# MAX232_0-99_Counter.net
KiCad netlist of a schematic drawn in Altium Designer
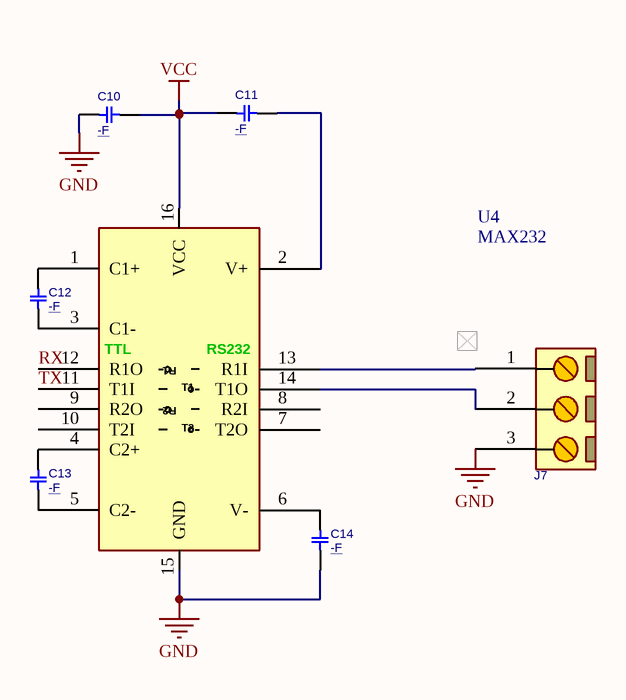
[diagram p0: MAX232_0-99_Counter.SchDoc]

(export (version "E")
  (design (tool "Eeschema 10.0.6"))
  (components
    (comp (ref "C10")
      (value "-F")
      (footprint "C0805")
      (description "CAP, MLCC, -F, -V, MATERIAL, -%, 0201")
      (fields (field (name "MANF_P#") "MANF_PART#"))
      (libsource (lib "all_lib") (part "CAP_SMD_MLCC_0805"))
    )
    (comp (ref "C11")
      (value "-F")
      (footprint "C0805")
      (description "CAP, MLCC, -F, -V, MATERIAL, -%, 0201")
      (fields (field (name "MANF_P#") "MANF_PART#"))
      (libsource (lib "all_lib") (part "CAP_SMD_MLCC_0805"))
    )
    (comp (ref "C12")
      (value "-F")
      (footprint "C0805")
      (description "CAP, MLCC, -F, -V, MATERIAL, -%, 0201")
      (fields (field (name "MANF_P#") "MANF_PART#"))
      (libsource (lib "all_lib") (part "CAP_SMD_MLCC_0805"))
    )
    (comp (ref "C13")
      (value "-F")
      (footprint "C0805")
      (description "CAP, MLCC, -F, -V, MATERIAL, -%, 0201")
      (fields (field (name "MANF_P#") "MANF_PART#"))
      (libsource (lib "all_lib") (part "CAP_SMD_MLCC_0805"))
    )
    (comp (ref "C14")
      (value "-F")
      (footprint "C0805")
      (description "CAP, MLCC, -F, -V, MATERIAL, -%, 0201")
      (fields (field (name "MANF_P#") "MANF_PART#"))
      (libsource (lib "all_lib") (part "CAP_SMD_MLCC_0805"))
    )
    (comp (ref "J7")
      (value "CONN_TB3")
      (footprint "MSTB_3")
      (description "CONN, PHOENIX MSTB, 5-G, 5.08mm pitch")
      (libsource (lib "all_lib") (part "CONN_MSTB_3"))
    )
    (comp (ref "U4")
      (value "MAX232")
      (footprint "SO_16")
      (description "RS-232, DUAL, +5V, Driver/Receiver")
      (fields (field (name "MANF") "Maxim Integrated") (field (name "MANF_PART#") "MAX232ACSE"))
      (libsource (lib "all_lib") (part "MAX232_SOP16"))
    )
  )
  (nets
    (net (code "1") (name "/RX") (class "Default")
      (node (ref "U4") (pin "12") (pinfunction "R1O_12") (pintype "passive"))
    )
    (net (code "2") (name "/TX") (class "Default")
      (node (ref "U4") (pin "11") (pinfunction "T1I_11") (pintype "passive"))
    )
    (net (code "3") (name "GND") (class "Default")
      (node (ref "C10") (pin "1") (pinfunction "1_1") (pintype "passive"))
      (node (ref "C14") (pin "1") (pinfunction "1_1") (pintype "passive"))
      (node (ref "J7") (pin "3") (pinfunction "3_3") (pintype "passive"))
      (node (ref "U4") (pin "15") (pinfunction "GND_15") (pintype "power_in"))
    )
    (net (code "4") (name "Net-(U4-C1+)") (class "Default")
      (node (ref "C12") (pin "2") (pinfunction "2_2") (pintype "passive"))
      (node (ref "U4") (pin "1") (pinfunction "C1+_1") (pintype "passive"))
    )
    (net (code "5") (name "Net-(U4-C1-)") (class "Default")
      (node (ref "C12") (pin "1") (pinfunction "1_1") (pintype "passive"))
      (node (ref "U4") (pin "3") (pinfunction "C1-_3") (pintype "passive"))
    )
    (net (code "6") (name "Net-(U4-C2+)") (class "Default")
      (node (ref "C13") (pin "2") (pinfunction "2_2") (pintype "passive"))
      (node (ref "U4") (pin "4") (pinfunction "C2+_4") (pintype "passive"))
    )
    (net (code "7") (name "Net-(U4-C2-)") (class "Default")
      (node (ref "C13") (pin "1") (pinfunction "1_1") (pintype "passive"))
      (node (ref "U4") (pin "5") (pinfunction "C2-_5") (pintype "passive"))
    )
    (net (code "8") (name "Net-(U4-R1I)") (class "Default")
      (node (ref "J7") (pin "1") (pinfunction "1_1") (pintype "passive"))
      (node (ref "U4") (pin "13") (pinfunction "R1I_13") (pintype "passive"))
    )
    (net (code "9") (name "Net-(U4-T1O)") (class "Default")
      (node (ref "J7") (pin "2") (pinfunction "2_2") (pintype "passive"))
      (node (ref "U4") (pin "14") (pinfunction "T1O_14") (pintype "passive"))
    )
    (net (code "10") (name "Net-(U4-V+)") (class "Default")
      (node (ref "C11") (pin "2") (pinfunction "2_2") (pintype "passive"))
      (node (ref "U4") (pin "2") (pinfunction "V+_2") (pintype "passive"))
    )
    (net (code "11") (name "Net-(U4-V-)") (class "Default")
      (node (ref "C14") (pin "2") (pinfunction "2_2") (pintype "passive"))
      (node (ref "U4") (pin "6") (pinfunction "V-_6") (pintype "passive"))
    )
    (net (code "12") (name "VCC") (class "Default")
      (node (ref "C10") (pin "2") (pinfunction "2_2") (pintype "passive"))
      (node (ref "C11") (pin "1") (pinfunction "1_1") (pintype "passive"))
      (node (ref "U4") (pin "16") (pinfunction "VCC_16") (pintype "power_in"))
    )
    (net (code "13") (name "unconnected-(U4-R2I-Pad8)") (class "Default")
      (node (ref "U4") (pin "8") (pinfunction "R2I_8") (pintype "passive"))
    )
    (net (code "14") (name "unconnected-(U4-R2O-Pad9)") (class "Default")
      (node (ref "U4") (pin "9") (pinfunction "R2O_9") (pintype "passive"))
    )
    (net (code "15") (name "unconnected-(U4-T2I-Pad10)") (class "Default")
      (node (ref "U4") (pin "10") (pinfunction "T2I_10") (pintype "passive"))
    )
    (net (code "16") (name "unconnected-(U4-T2O-Pad7)") (class "Default")
      (node (ref "U4") (pin "7") (pinfunction "T2O_7") (pintype "passive"))
    )
  )
)
